# Sheet1.net
KiCad netlist of a schematic drawn in Altium Designer
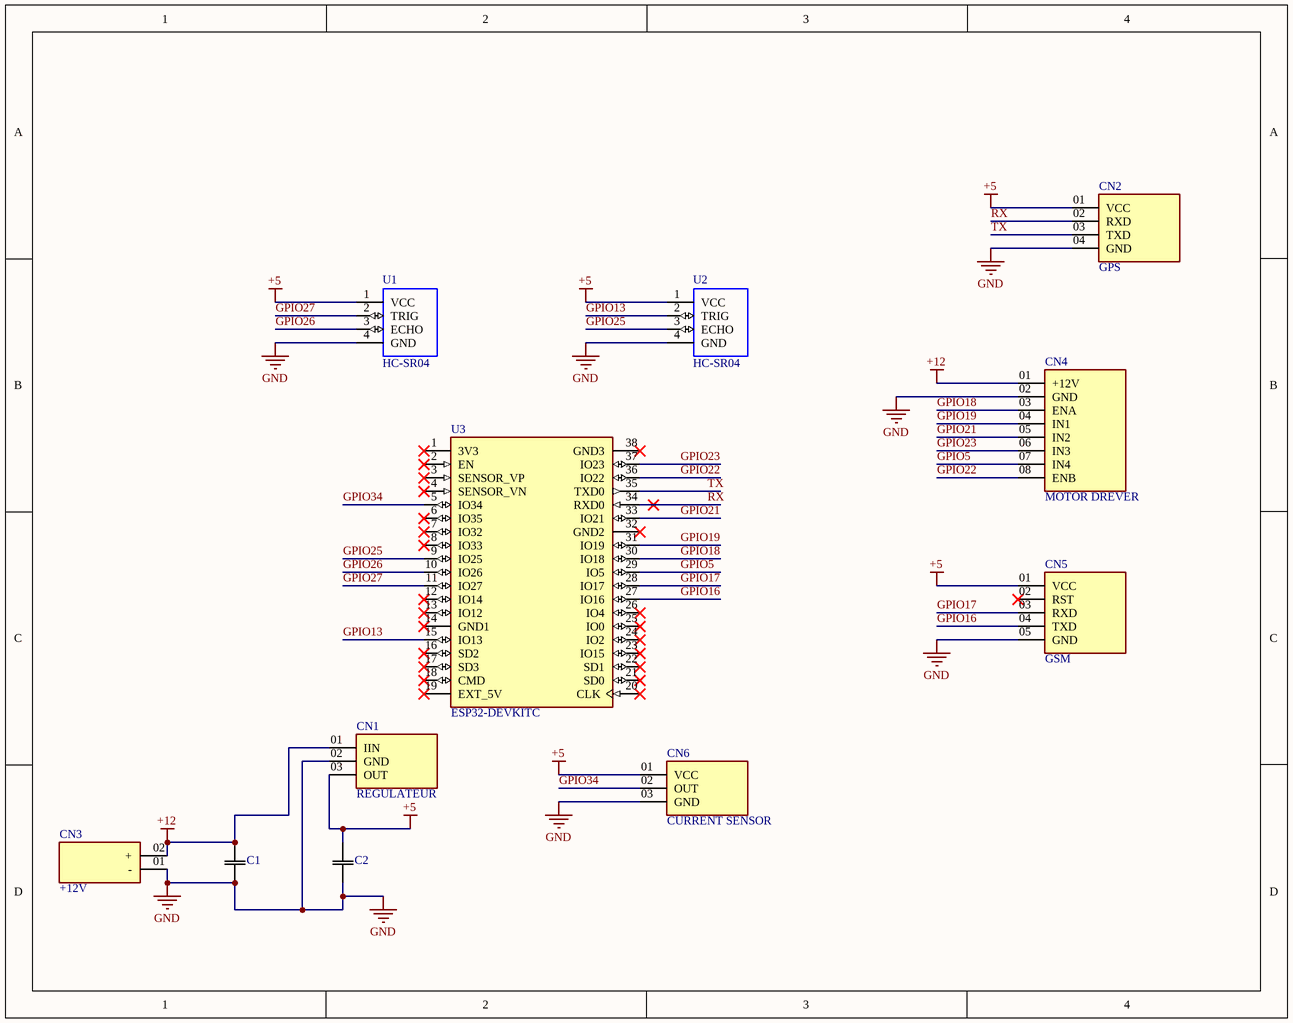
[diagram p0: Sheet1.SchDoc]

(export (version "E")
  (design (tool "Eeschema 10.0.6"))
  (components
    (comp (ref "C1")
      (value "ECE-A1CKS100")
      (footprint "CAP_4 X 5_PAN")
      (description "No Description Available")
      (libsource (lib "ProjecrSchematicLibrary") (part "ECE-A1CKS100"))
    )
    (comp (ref "C2")
      (value "ECE-A1CKS100")
      (footprint "CAP_4 X 5_PAN")
      (description "No Description Available")
      (libsource (lib "ProjecrSchematicLibrary") (part "ECE-A1CKS100"))
    )
    (comp (ref "CN1")
      (value "REGULATEUR")
      (footprint "SAMTEC_BCS-103-L-S-TE")
      (fields (field (name "MF") "Samtec") (field (name "MP") "BCS-103-L-S-TE"))
      (libsource (lib "ProjecrSchematicLibrary") (part "BCS-103-L-S-TE"))
    )
    (comp (ref "CN2")
      (value "GPS")
      (footprint "SAMTEC_BCS-104-F-S-TE")
      (description "4 Position Receptacle Connector 0.100 (2.54mm) Through Hole Gold")
      (fields (field (name "MF") "Samtec") (field (name "DIGI-KEY_PART_NUMBER") "BCS-104-F-S-TE-ND"))
      (libsource (lib "ProjecrSchematicLibrary") (part "BCS-104-F-S-TE"))
    )
    (comp (ref "CN3")
      (value "+12V")
      (footprint "SAMTEC_BCS-102-F-S-TE")
      (fields (field (name "MP") "BCS-102-F-S-TE") (field (name "MF") "Samtec Inc."))
      (libsource (lib "ProjecrSchematicLibrary") (part "BCS-102-F-S-TE"))
    )
    (comp (ref "CN4")
      (value "MOTOR DREVER")
      (footprint "SAMTEC_BCS-108-F-S-TE")
      (fields (field (name "MF") "Samtec") (field (name "MP") "BCS-108-F-S-TE"))
      (libsource (lib "ProjecrSchematicLibrary") (part "BCS-108-F-S-TE"))
    )
    (comp (ref "CN5")
      (value "GSM")
      (footprint "SAMTEC_BCS-105-F-S-TE")
      (fields (field (name "MF") "Samtec") (field (name "MP") "BCS-105-F-S-TE"))
      (libsource (lib "ProjecrSchematicLibrary") (part "BCS-105-F-S-TE"))
    )
    (comp (ref "CN6")
      (value "CURRENT SENSOR")
      (footprint "SAMTEC_BCS-103-L-S-TE")
      (fields (field (name "MF") "Samtec") (field (name "MP") "BCS-103-L-S-TE"))
      (libsource (lib "ProjecrSchematicLibrary") (part "BCS-103-L-S-TE"))
    )
    (comp (ref "U1")
      (value "HC-SR04")
      (footprint "XCVR_HC-SR04")
      (description "Ultrasonic Sensor Module")
      (libsource (lib "ProjecrSchematicLibrary") (part "HC-SR04"))
    )
    (comp (ref "U2")
      (value "HC-SR04")
      (footprint "XCVR_HC-SR04")
      (description "Ultrasonic Sensor Module")
      (libsource (lib "ProjecrSchematicLibrary") (part "HC-SR04"))
    )
    (comp (ref "U3")
      (value "ESP32-DEVKITC")
      (footprint "MODULE_ESP32-DEVKITC - duplicate")
      (fields (field (name "MF") "Espressif Systems"))
      (libsource (lib "ProjecrSchematicLibrary") (part "ESP32-DEVKITC"))
    )
  )
  (nets
    (net (code "1") (name "+5") (class "Default")
      (node (ref "C2") (pin "2") (pinfunction "2_2") (pintype "passive"))
      (node (ref "CN1") (pin "03") (pinfunction "OUT_03") (pintype "passive"))
      (node (ref "CN2") (pin "01") (pinfunction "VCC_01") (pintype "passive"))
      (node (ref "CN5") (pin "01") (pinfunction "VCC_01") (pintype "passive"))
      (node (ref "CN6") (pin "01") (pinfunction "IIN_01") (pintype "passive"))
      (node (ref "U1") (pin "1") (pinfunction "VCC_1") (pintype "power_in"))
      (node (ref "U2") (pin "1") (pinfunction "VCC_1") (pintype "power_in"))
    )
    (net (code "2") (name "+12") (class "Default")
      (node (ref "C1") (pin "2") (pinfunction "2_2") (pintype "passive"))
      (node (ref "CN1") (pin "01") (pinfunction "IIN_01") (pintype "passive"))
      (node (ref "CN3") (pin "02") (pinfunction "+_02") (pintype "passive"))
      (node (ref "CN4") (pin "01") (pinfunction "+12V_01") (pintype "passive"))
    )
    (net (code "3") (name "/GPIO5") (class "Default")
      (node (ref "CN4") (pin "07") (pinfunction "IN4_07") (pintype "passive"))
      (node (ref "U3") (pin "29") (pinfunction "IO5_29") (pintype "bidirectional"))
    )
    (net (code "4") (name "/GPIO13") (class "Default")
      (node (ref "U2") (pin "2") (pinfunction "TRIG_2") (pintype "bidirectional"))
      (node (ref "U3") (pin "15") (pinfunction "IO13_15") (pintype "bidirectional"))
    )
    (net (code "5") (name "/GPIO16") (class "Default")
      (node (ref "CN5") (pin "04") (pinfunction "TXD_04") (pintype "passive"))
      (node (ref "U3") (pin "27") (pinfunction "IO16_27") (pintype "bidirectional"))
    )
    (net (code "6") (name "/GPIO17") (class "Default")
      (node (ref "CN5") (pin "03") (pinfunction "RXD_03") (pintype "passive"))
      (node (ref "U3") (pin "28") (pinfunction "IO17_28") (pintype "bidirectional"))
    )
    (net (code "7") (name "/GPIO18") (class "Default")
      (node (ref "CN4") (pin "03") (pinfunction "ENA_03") (pintype "passive"))
      (node (ref "U3") (pin "30") (pinfunction "IO18_30") (pintype "bidirectional"))
    )
    (net (code "8") (name "/GPIO19") (class "Default")
      (node (ref "CN4") (pin "04") (pinfunction "IN1_04") (pintype "passive"))
      (node (ref "U3") (pin "31") (pinfunction "IO19_31") (pintype "bidirectional"))
    )
    (net (code "9") (name "/GPIO21") (class "Default")
      (node (ref "CN4") (pin "05") (pinfunction "IN2_05") (pintype "passive"))
      (node (ref "U3") (pin "33") (pinfunction "IO21_33") (pintype "bidirectional"))
    )
    (net (code "10") (name "/GPIO22") (class "Default")
      (node (ref "CN4") (pin "08") (pinfunction "ENB_08") (pintype "passive"))
      (node (ref "U3") (pin "36") (pinfunction "IO22_36") (pintype "bidirectional"))
    )
    (net (code "11") (name "/GPIO23") (class "Default")
      (node (ref "CN4") (pin "06") (pinfunction "IN3_06") (pintype "passive"))
      (node (ref "U3") (pin "37") (pinfunction "IO23_37") (pintype "bidirectional"))
    )
    (net (code "12") (name "/GPIO25") (class "Default")
      (node (ref "U2") (pin "3") (pinfunction "ECHO_3") (pintype "bidirectional"))
      (node (ref "U3") (pin "9") (pinfunction "IO25_9") (pintype "bidirectional"))
    )
    (net (code "13") (name "/GPIO26") (class "Default")
      (node (ref "U1") (pin "3") (pinfunction "ECHO_3") (pintype "bidirectional"))
      (node (ref "U3") (pin "10") (pinfunction "IO26_10") (pintype "bidirectional"))
    )
    (net (code "14") (name "/GPIO27") (class "Default")
      (node (ref "U1") (pin "2") (pinfunction "TRIG_2") (pintype "bidirectional"))
      (node (ref "U3") (pin "11") (pinfunction "IO27_11") (pintype "bidirectional"))
    )
    (net (code "15") (name "/GPIO34") (class "Default")
      (node (ref "CN6") (pin "02") (pinfunction "GND_02") (pintype "passive"))
      (node (ref "U3") (pin "5") (pinfunction "IO34_5") (pintype "bidirectional"))
    )
    (net (code "16") (name "/RX") (class "Default")
      (node (ref "CN2") (pin "02") (pinfunction "RXD_02") (pintype "passive"))
      (node (ref "U3") (pin "34") (pinfunction "RXD0_34") (pintype "input"))
    )
    (net (code "17") (name "/TX") (class "Default")
      (node (ref "CN2") (pin "03") (pinfunction "TXD_03") (pintype "passive"))
      (node (ref "U3") (pin "35") (pinfunction "TXD0_35") (pintype "output"))
    )
    (net (code "18") (name "GND") (class "Default")
      (node (ref "C1") (pin "1") (pinfunction "1_1") (pintype "passive"))
      (node (ref "C2") (pin "1") (pinfunction "1_1") (pintype "passive"))
      (node (ref "CN1") (pin "02") (pinfunction "GND_02") (pintype "passive"))
      (node (ref "CN2") (pin "04") (pinfunction "GND_04") (pintype "passive"))
      (node (ref "CN3") (pin "01") (pinfunction "-_01") (pintype "passive"))
      (node (ref "CN4") (pin "02") (pinfunction "GND_02") (pintype "passive"))
      (node (ref "CN5") (pin "05") (pinfunction "GND_05") (pintype "passive"))
      (node (ref "CN6") (pin "03") (pinfunction "OUT_03") (pintype "passive"))
      (node (ref "U1") (pin "4") (pinfunction "GND_4") (pintype "power_in"))
      (node (ref "U2") (pin "4") (pinfunction "GND_4") (pintype "power_in"))
    )
    (net (code "19") (name "unconnected-(CN5-RST-Pad02)") (class "Default")
      (node (ref "CN5") (pin "02") (pinfunction "RST_02") (pintype "passive+no_connect"))
    )
    (net (code "20") (name "unconnected-(U3-3V3-Pad1)") (class "Default")
      (node (ref "U3") (pin "1") (pinfunction "3V3_1") (pintype "power_in+no_connect"))
    )
    (net (code "21") (name "unconnected-(U3-CLK-Pad20)") (class "Default")
      (node (ref "U3") (pin "20") (pinfunction "CLK_20") (pintype "input+no_connect"))
    )
    (net (code "22") (name "unconnected-(U3-CMD-Pad18)") (class "Default")
      (node (ref "U3") (pin "18") (pinfunction "CMD_18") (pintype "bidirectional+no_connect"))
    )
    (net (code "23") (name "unconnected-(U3-EN-Pad2)") (class "Default")
      (node (ref "U3") (pin "2") (pinfunction "EN_2") (pintype "input+no_connect"))
    )
    (net (code "24") (name "unconnected-(U3-EXT_5V-Pad19)") (class "Default")
      (node (ref "U3") (pin "19") (pinfunction "EXT_5V_19") (pintype "power_in+no_connect"))
    )
    (net (code "25") (name "unconnected-(U3-GND1-Pad14)") (class "Default")
      (node (ref "U3") (pin "14") (pinfunction "GND1_14") (pintype "power_in+no_connect"))
    )
    (net (code "26") (name "unconnected-(U3-GND2-Pad32)") (class "Default")
      (node (ref "U3") (pin "32") (pinfunction "GND2_32") (pintype "power_in+no_connect"))
    )
    (net (code "27") (name "unconnected-(U3-GND3-Pad38)") (class "Default")
      (node (ref "U3") (pin "38") (pinfunction "GND3_38") (pintype "power_in+no_connect"))
    )
    (net (code "28") (name "unconnected-(U3-IO0-Pad25)") (class "Default")
      (node (ref "U3") (pin "25") (pinfunction "IO0_25") (pintype "bidirectional+no_connect"))
    )
    (net (code "29") (name "unconnected-(U3-IO2-Pad24)") (class "Default")
      (node (ref "U3") (pin "24") (pinfunction "IO2_24") (pintype "bidirectional+no_connect"))
    )
    (net (code "30") (name "unconnected-(U3-IO4-Pad26)") (class "Default")
      (node (ref "U3") (pin "26") (pinfunction "IO4_26") (pintype "bidirectional+no_connect"))
    )
    (net (code "31") (name "unconnected-(U3-IO12-Pad13)") (class "Default")
      (node (ref "U3") (pin "13") (pinfunction "IO12_13") (pintype "bidirectional+no_connect"))
    )
    (net (code "32") (name "unconnected-(U3-IO14-Pad12)") (class "Default")
      (node (ref "U3") (pin "12") (pinfunction "IO14_12") (pintype "bidirectional+no_connect"))
    )
    (net (code "33") (name "unconnected-(U3-IO15-Pad23)") (class "Default")
      (node (ref "U3") (pin "23") (pinfunction "IO15_23") (pintype "bidirectional+no_connect"))
    )
    (net (code "34") (name "unconnected-(U3-IO32-Pad7)") (class "Default")
      (node (ref "U3") (pin "7") (pinfunction "IO32_7") (pintype "bidirectional+no_connect"))
    )
    (net (code "35") (name "unconnected-(U3-IO33-Pad8)") (class "Default")
      (node (ref "U3") (pin "8") (pinfunction "IO33_8") (pintype "bidirectional+no_connect"))
    )
    (net (code "36") (name "unconnected-(U3-IO35-Pad6)") (class "Default")
      (node (ref "U3") (pin "6") (pinfunction "IO35_6") (pintype "bidirectional+no_connect"))
    )
    (net (code "37") (name "unconnected-(U3-SD0-Pad21)") (class "Default")
      (node (ref "U3") (pin "21") (pinfunction "SD0_21") (pintype "bidirectional+no_connect"))
    )
    (net (code "38") (name "unconnected-(U3-SD1-Pad22)") (class "Default")
      (node (ref "U3") (pin "22") (pinfunction "SD1_22") (pintype "bidirectional+no_connect"))
    )
    (net (code "39") (name "unconnected-(U3-SD2-Pad16)") (class "Default")
      (node (ref "U3") (pin "16") (pinfunction "SD2_16") (pintype "bidirectional+no_connect"))
    )
    (net (code "40") (name "unconnected-(U3-SD3-Pad17)") (class "Default")
      (node (ref "U3") (pin "17") (pinfunction "SD3_17") (pintype "bidirectional+no_connect"))
    )
    (net (code "41") (name "unconnected-(U3-SENSOR_VN-Pad4)") (class "Default")
      (node (ref "U3") (pin "4") (pinfunction "SENSOR_VN_4") (pintype "input+no_connect"))
    )
    (net (code "42") (name "unconnected-(U3-SENSOR_VP-Pad3)") (class "Default")
      (node (ref "U3") (pin "3") (pinfunction "SENSOR_VP_3") (pintype "input+no_connect"))
    )
  )
)
